# Output.net
KiCad netlist of a schematic drawn in Altium Designer
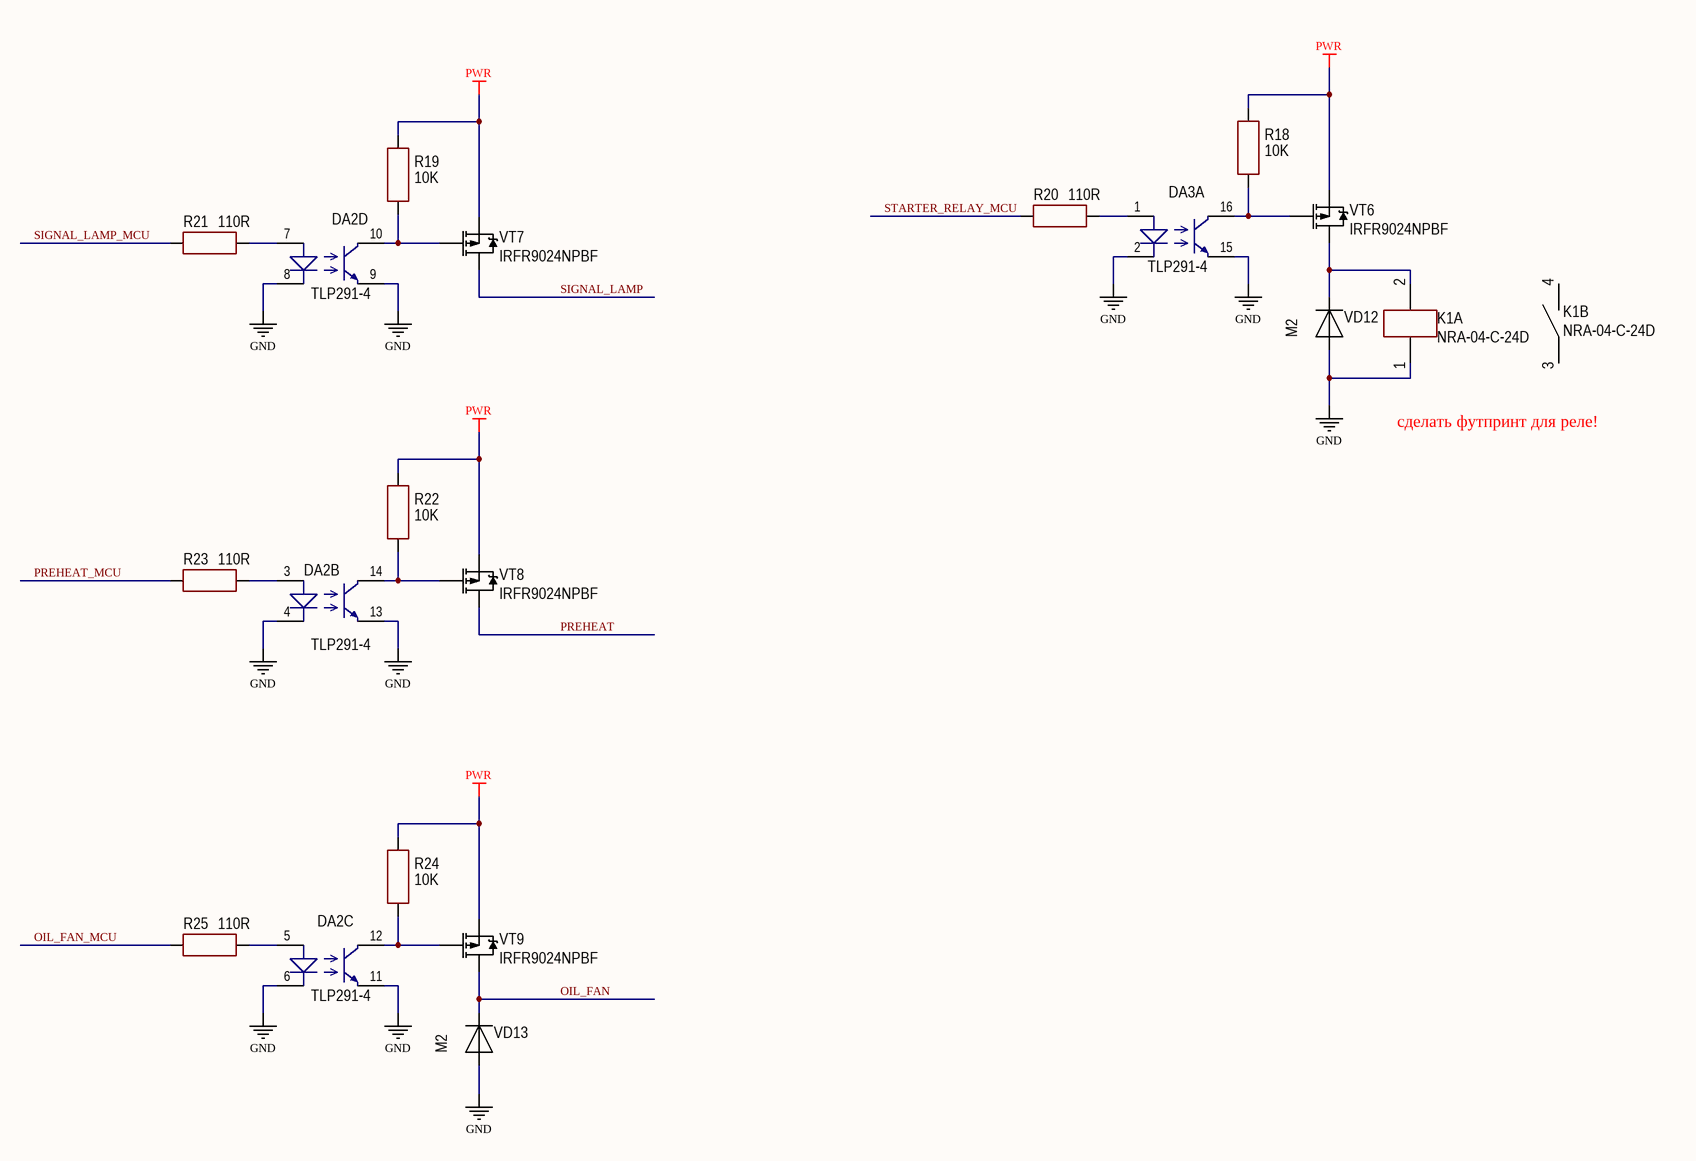
[diagram p0: Output.SchDoc]

(export (version "E")
  (design (tool "Eeschema 10.0.6"))
  (components
    (comp (ref "DA2") (value "TLP291-4") (footprint "SOP16") (libsource (lib "my_library") (part "TLP291-4")))
    (comp (ref "DA3") (value "TLP291-4") (footprint "SOP16") (libsource (lib "my_library") (part "TLP291-4")))
    (comp (ref "K1")
      (value "~")
      (footprint "REL: T9GS1")
      (fields
        (field (name "MANUFACTURER") "TE Connectivity")
        (field (name "VALUEMANUFACTURERPARTNUMBER") "Electromechanics relay, 12VDC, 480VAC, 30A, 1NO, -40...+85°C")
        (field (name "PARTNUMBER") "NRA-04-C-24D")
      )
      (libsource (lib "electromechanics") (part "Relay_T9GS1L14"))
    )
    (comp (ref "R18")
      (value "10K")
      (footprint "RES: 1206")
      (fields
        (field (name "MANUFACTURER") "Yageo")
        (field (name "PARTNUMBER") "RC1206JR-07100RL")
        (field (name "VALUEMANUFACTURERPARTNUMBER") "Resistor film, 10K, ±5%, 1206, 0.25W, -55...+125°C")
      )
      (libsource (lib "") (part "Resistor_1206_1"))
    )
    (comp (ref "R19")
      (value "10K")
      (footprint "RES: 1206")
      (fields
        (field (name "MANUFACTURER") "Yageo")
        (field (name "PARTNUMBER") "RC1206JR-07100RL")
        (field (name "VALUEMANUFACTURERPARTNUMBER") "Resistor film, 10K, ±5%, 1206, 0.25W, -55...+125°C")
      )
      (libsource (lib "") (part "Resistor_1206_1"))
    )
    (comp (ref "R20")
      (value "110R")
      (footprint "RES: 1206")
      (fields
        (field (name "MANUFACTURER") "Yageo")
        (field (name "PARTNUMBER") "RC1206JR-07100RL")
        (field (name "VALUEMANUFACTURERPARTNUMBER") "Resistor film, 110R, ±5%, 1206, 0.25W, -55...+125°C")
      )
      (libsource (lib "resistor") (part "Resistor_1206"))
    )
    (comp (ref "R21")
      (value "110R")
      (footprint "RES: 1206")
      (fields
        (field (name "MANUFACTURER") "Yageo")
        (field (name "PARTNUMBER") "RC1206JR-07100RL")
        (field (name "VALUEMANUFACTURERPARTNUMBER") "Resistor film, 110R, ±5%, 1206, 0.25W, -55...+125°C")
      )
      (libsource (lib "resistor") (part "Resistor_1206"))
    )
    (comp (ref "R22")
      (value "10K")
      (footprint "RES: 1206")
      (fields
        (field (name "MANUFACTURER") "Yageo")
        (field (name "PARTNUMBER") "RC1206JR-07100RL")
        (field (name "VALUEMANUFACTURERPARTNUMBER") "Resistor film, 10K, ±5%, 1206, 0.25W, -55...+125°C")
      )
      (libsource (lib "") (part "Resistor_1206_1"))
    )
    (comp (ref "R23")
      (value "110R")
      (footprint "RES: 1206")
      (fields
        (field (name "MANUFACTURER") "Yageo")
        (field (name "PARTNUMBER") "RC1206JR-07100RL")
        (field (name "VALUEMANUFACTURERPARTNUMBER") "Resistor film, 110R, ±5%, 1206, 0.25W, -55...+125°C")
      )
      (libsource (lib "resistor") (part "Resistor_1206"))
    )
    (comp (ref "R24")
      (value "10K")
      (footprint "RES: 1206")
      (fields
        (field (name "MANUFACTURER") "Yageo")
        (field (name "PARTNUMBER") "RC1206JR-07100RL")
        (field (name "VALUEMANUFACTURERPARTNUMBER") "Resistor film, 10K, ±5%, 1206, 0.25W, -55...+125°C")
      )
      (libsource (lib "") (part "Resistor_1206_1"))
    )
    (comp (ref "R25")
      (value "110R")
      (footprint "RES: 1206")
      (fields
        (field (name "MANUFACTURER") "Yageo")
        (field (name "PARTNUMBER") "RC1206JR-07100RL")
        (field (name "VALUEMANUFACTURERPARTNUMBER") "Resistor film, 110R, ±5%, 1206, 0.25W, -55...+125°C")
      )
      (libsource (lib "resistor") (part "Resistor_1206"))
    )
    (comp (ref "VD12")
      (value "~")
      (footprint "DIODE: SMA")
      (fields
        (field (name "MANUFACTURER") "Micro Commercial")
        (field (name "VALUEMANUFACTURERPARTNUMBER") "Single diode, 75V, 150mA, 1V, 4ns, SOD-323, -55...+150°C")
        (field (name "VOLTAGE") "75V")
        (field (name "PARTNUMBER") "M2")
      )
      (libsource (lib "diode") (part "Diode_single"))
    )
    (comp (ref "VD13")
      (value "~")
      (footprint "DIODE: SMA")
      (fields
        (field (name "MANUFACTURER") "Micro Commercial")
        (field (name "VALUEMANUFACTURERPARTNUMBER") "Single diode, 75V, 150mA, 1V, 4ns, SOD-323, -55...+150°C")
        (field (name "VOLTAGE") "75V")
        (field (name "PARTNUMBER") "M2")
      )
      (libsource (lib "diode") (part "Diode_single"))
    )
    (comp (ref "VT6")
      (value "~")
      (footprint "DPAK")
      (fields
        (field (name "MANUFACTURER") "Infineon Technologies")
        (field (name "VALUEMANUFACTURERPARTNUMBER") "MOSFET P-channel transistor, 20V, 2.6A, 2.9nC, 2.5W, 135mOhm, 220pF, SOT-23, -55...+150°C")
        (field (name "PARTNUMBER") "IRFR9024NPBF")
      )
      (libsource (lib "transistor") (part "MOSFET_P_123"))
    )
    (comp (ref "VT7")
      (value "~")
      (footprint "DPAK")
      (fields
        (field (name "MANUFACTURER") "Infineon Technologies")
        (field (name "VALUEMANUFACTURERPARTNUMBER") "MOSFET P-channel transistor, 20V, 2.6A, 2.9nC, 2.5W, 135mOhm, 220pF, SOT-23, -55...+150°C")
        (field (name "PARTNUMBER") "IRFR9024NPBF")
      )
      (libsource (lib "transistor") (part "MOSFET_P_123"))
    )
    (comp (ref "VT8")
      (value "~")
      (footprint "DPAK")
      (fields
        (field (name "MANUFACTURER") "Infineon Technologies")
        (field (name "VALUEMANUFACTURERPARTNUMBER") "MOSFET P-channel transistor, 20V, 2.6A, 2.9nC, 2.5W, 135mOhm, 220pF, SOT-23, -55...+150°C")
        (field (name "PARTNUMBER") "IRFR9024NPBF")
      )
      (libsource (lib "transistor") (part "MOSFET_P_123"))
    )
    (comp (ref "VT9")
      (value "~")
      (footprint "DPAK")
      (fields
        (field (name "MANUFACTURER") "Infineon Technologies")
        (field (name "VALUEMANUFACTURERPARTNUMBER") "MOSFET P-channel transistor, 20V, 2.6A, 2.9nC, 2.5W, 135mOhm, 220pF, SOT-23, -55...+150°C")
        (field (name "PARTNUMBER") "IRFR9024NPBF")
      )
      (libsource (lib "transistor") (part "MOSFET_P_123"))
    )
  )
  (nets
    (net (code "1") (name "/OIL_FAN") (class "Default")
      (node (ref "VD13") (pin "2") (pinfunction "2_2") (pintype "passive"))
      (node (ref "VT9") (pin "2") (pinfunction "D_2") (pintype "passive"))
    )
    (net (code "2") (name "/OIL_FAN_MCU") (class "Default")
      (node (ref "R25") (pin "2") (pinfunction "2_2") (pintype "passive"))
    )
    (net (code "3") (name "/PREHEAT") (class "Default")
      (node (ref "VT8") (pin "2") (pinfunction "D_2") (pintype "passive"))
    )
    (net (code "4") (name "/PREHEAT_MCU") (class "Default")
      (node (ref "R23") (pin "2") (pinfunction "2_2") (pintype "passive"))
    )
    (net (code "5") (name "/SIGNAL_LAMP") (class "Default")
      (node (ref "VT7") (pin "2") (pinfunction "D_2") (pintype "passive"))
    )
    (net (code "6") (name "/SIGNAL_LAMP_MCU") (class "Default")
      (node (ref "R21") (pin "2") (pinfunction "2_2") (pintype "passive"))
    )
    (net (code "7") (name "/STARTER_RELAY_MCU") (class "Default")
      (node (ref "R20") (pin "2") (pinfunction "2_2") (pintype "passive"))
    )
    (net (code "8") (name "GND") (class "Default")
      (node (ref "DA2") (pin "11") (pinfunction "11_11") (pintype "passive"))
      (node (ref "DA2") (pin "13") (pinfunction "13_13") (pintype "passive"))
      (node (ref "DA2") (pin "4") (pinfunction "4_4") (pintype "passive"))
      (node (ref "DA2") (pin "6") (pinfunction "6_6") (pintype "passive"))
      (node (ref "DA2") (pin "8") (pinfunction "8_8") (pintype "passive"))
      (node (ref "DA2") (pin "9") (pinfunction "9_9") (pintype "passive"))
      (node (ref "DA3") (pin "15") (pinfunction "15_15") (pintype "passive"))
      (node (ref "DA3") (pin "2") (pinfunction "2_2") (pintype "passive"))
      (node (ref "K1") (pin "1") (pinfunction "1_1") (pintype "passive"))
      (node (ref "VD12") (pin "1") (pinfunction "1_1") (pintype "passive"))
      (node (ref "VD13") (pin "1") (pinfunction "1_1") (pintype "passive"))
    )
    (net (code "9") (name "Net-(DA2-Pad3)") (class "Default")
      (node (ref "DA2") (pin "3") (pinfunction "3_3") (pintype "passive"))
      (node (ref "R23") (pin "1") (pinfunction "1_1") (pintype "passive"))
    )
    (net (code "10") (name "Net-(DA2-Pad5)") (class "Default")
      (node (ref "DA2") (pin "5") (pinfunction "5_5") (pintype "passive"))
      (node (ref "R25") (pin "1") (pinfunction "1_1") (pintype "passive"))
    )
    (net (code "11") (name "Net-(DA2-Pad7)") (class "Default")
      (node (ref "DA2") (pin "7") (pinfunction "7_7") (pintype "passive"))
      (node (ref "R21") (pin "1") (pinfunction "1_1") (pintype "passive"))
    )
    (net (code "12") (name "Net-(DA3-Pad1)") (class "Default")
      (node (ref "DA3") (pin "1") (pinfunction "1_1") (pintype "passive"))
      (node (ref "R20") (pin "1") (pinfunction "1_1") (pintype "passive"))
    )
    (net (code "13") (name "Net-(VT6-D)") (class "Default")
      (node (ref "K1") (pin "2") (pinfunction "2_2") (pintype "passive"))
      (node (ref "VD12") (pin "2") (pinfunction "2_2") (pintype "passive"))
      (node (ref "VT6") (pin "2") (pinfunction "D_2") (pintype "passive"))
    )
    (net (code "14") (name "Net-(VT6-G)") (class "Default")
      (node (ref "DA3") (pin "16") (pinfunction "16_16") (pintype "passive"))
      (node (ref "R18") (pin "1") (pinfunction "1_1") (pintype "passive"))
      (node (ref "VT6") (pin "1") (pinfunction "G_1") (pintype "passive"))
    )
    (net (code "15") (name "Net-(VT7-G)") (class "Default")
      (node (ref "DA2") (pin "10") (pinfunction "10_10") (pintype "passive"))
      (node (ref "R19") (pin "1") (pinfunction "1_1") (pintype "passive"))
      (node (ref "VT7") (pin "1") (pinfunction "G_1") (pintype "passive"))
    )
    (net (code "16") (name "Net-(VT8-G)") (class "Default")
      (node (ref "DA2") (pin "14") (pinfunction "14_14") (pintype "passive"))
      (node (ref "R22") (pin "1") (pinfunction "1_1") (pintype "passive"))
      (node (ref "VT8") (pin "1") (pinfunction "G_1") (pintype "passive"))
    )
    (net (code "17") (name "Net-(VT9-G)") (class "Default")
      (node (ref "DA2") (pin "12") (pinfunction "12_12") (pintype "passive"))
      (node (ref "R24") (pin "1") (pinfunction "1_1") (pintype "passive"))
      (node (ref "VT9") (pin "1") (pinfunction "G_1") (pintype "passive"))
    )
    (net (code "18") (name "PWR") (class "Default")
      (node (ref "R18") (pin "2") (pinfunction "2_2") (pintype "passive"))
      (node (ref "R19") (pin "2") (pinfunction "2_2") (pintype "passive"))
      (node (ref "R22") (pin "2") (pinfunction "2_2") (pintype "passive"))
      (node (ref "R24") (pin "2") (pinfunction "2_2") (pintype "passive"))
      (node (ref "VT6") (pin "3") (pinfunction "S_3") (pintype "passive"))
      (node (ref "VT7") (pin "3") (pinfunction "S_3") (pintype "passive"))
      (node (ref "VT8") (pin "3") (pinfunction "S_3") (pintype "passive"))
      (node (ref "VT9") (pin "3") (pinfunction "S_3") (pintype "passive"))
    )
    (net (code "19") (name "unconnected-(K1-Pad3)") (class "Default")
      (node (ref "K1") (pin "3") (pinfunction "3_3") (pintype "passive"))
    )
    (net (code "20") (name "unconnected-(K1-Pad4)") (class "Default")
      (node (ref "K1") (pin "4") (pinfunction "4_4") (pintype "passive"))
    )
  )
)
